# NFC_Card.net
KiCad netlist of a schematic drawn in EasyEDA
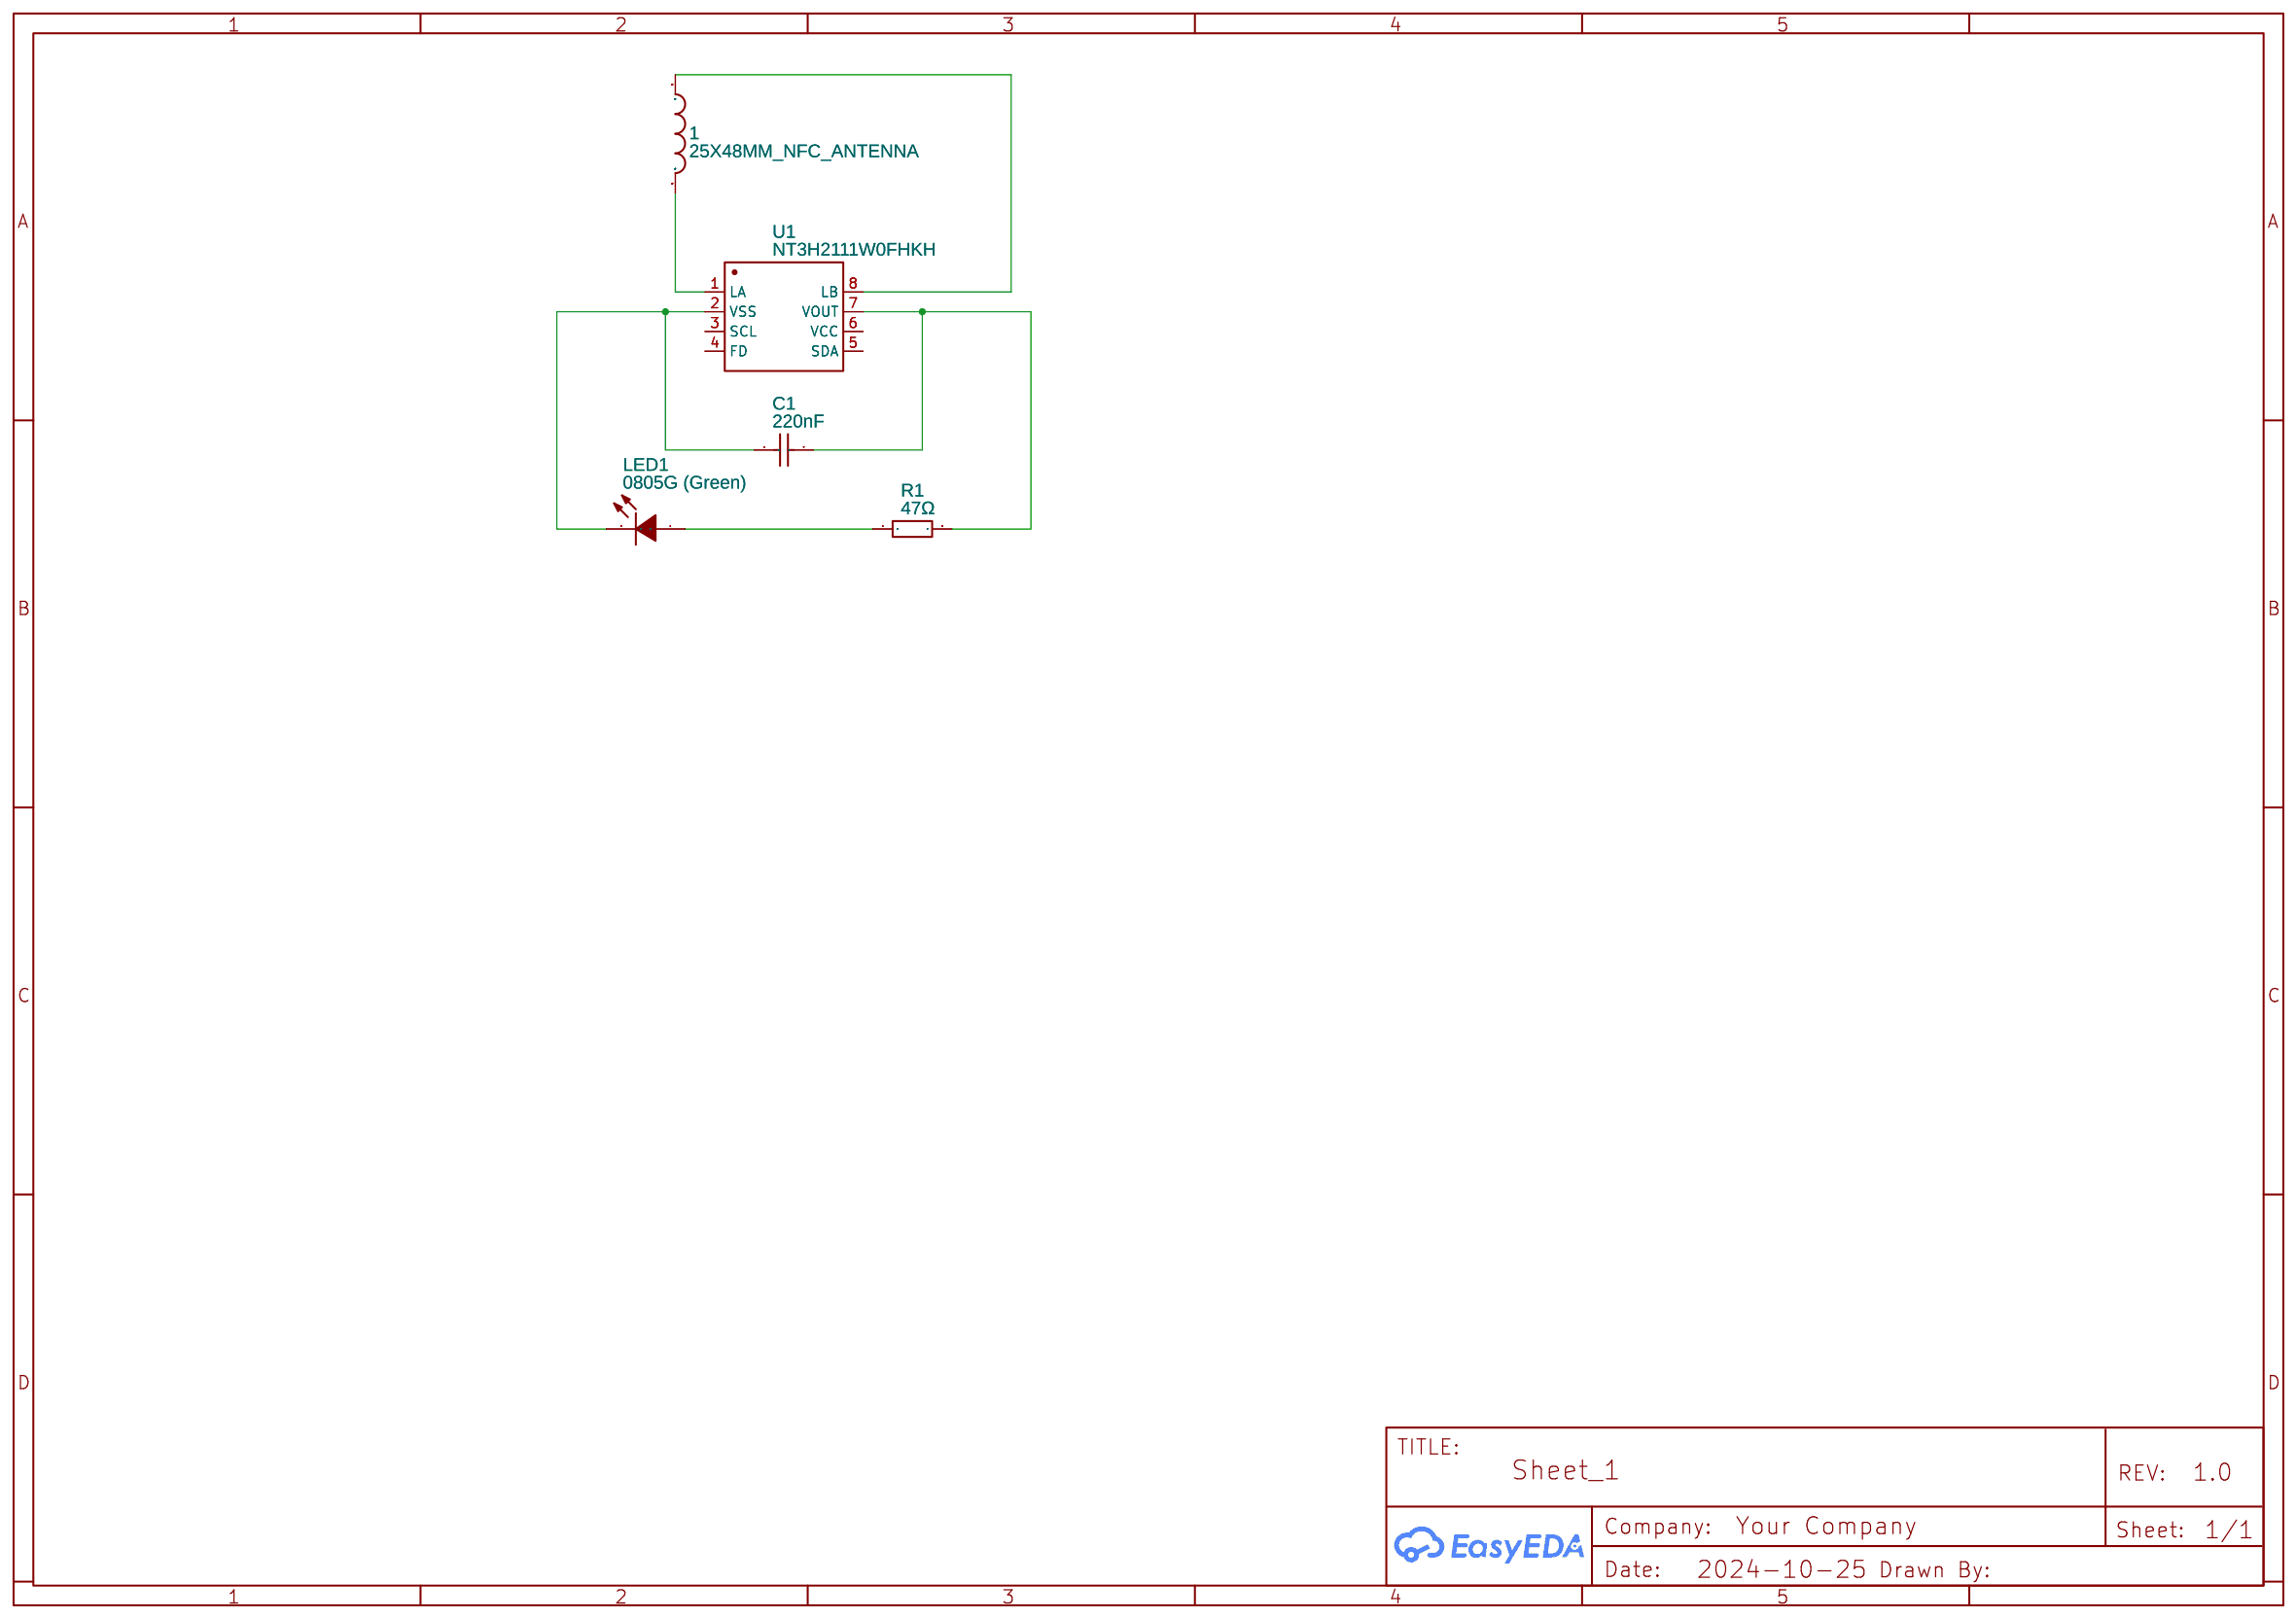
[diagram p0: schematic sheet]

(export (version "E")
  (design (tool "Eeschema 10.0.6"))
  (components
    (comp (ref "1") (value "25X48MM_NFC_ANTENNA") (libsource (lib "") (part "25X48MM_NFC_ANTENNA")))
    (comp (ref "C1")
      (value "220nF")
      (fields
        (field (name "Manufacturer Part") "CL10B224KA8NNNC")
        (field (name "Manufacturer") "SAMSUNG(三星)")
      )
      (libsource (lib "") (part "CL10B224KA8NNNC"))
    )
    (comp (ref "LED1")
      (value "0805G (Green)")
      (fields (field (name "Manufacturer Part") "KT-0805G") (field (name "Manufacturer") "KENTO"))
      (libsource (lib "") (part "0805G (Green)"))
    )
    (comp (ref "R1")
      (value "47Ω")
      (fields
        (field (name "Manufacturer Part") "0603WAF470JT5E")
        (field (name "Manufacturer") "UNI-ROYAL(厚声)")
      )
      (libsource (lib "") (part "0603WAF470JT5E"))
    )
    (comp (ref "U1")
      (value "NT3H2111W0FHKH")
      (fields (field (name "Manufacturer") "NXP(恩智浦)"))
      (libsource (lib "") (part "NT3H2111W0FHKH"))
    )
  )
  (nets
    (net (code "1") (name "Net-(LED1-A)") (class "Default")
      (node (ref "LED1") (pin "1") (pinfunction "A_1") (pintype "unspecified"))
      (node (ref "R1") (pin "1") (pinfunction "1_1") (pintype "input"))
    )
    (net (code "2") (name "Net-(LED1-K)") (class "Default")
      (node (ref "C1") (pin "1") (pinfunction "1_1") (pintype "input"))
      (node (ref "LED1") (pin "2") (pinfunction "K_2") (pintype "unspecified"))
      (node (ref "U1") (pin "2") (pinfunction "VSS_2") (pintype "unspecified"))
    )
    (net (code "3") (name "Net-(U1-LA)") (class "Default")
      (node (ref "1") (pin "P$2") (pinfunction "P$2_P$2") (pintype "bidirectional"))
      (node (ref "U1") (pin "1") (pinfunction "LA_1") (pintype "unspecified"))
    )
    (net (code "4") (name "Net-(U1-LB)") (class "Default")
      (node (ref "1") (pin "P$1") (pinfunction "P$1_P$1") (pintype "bidirectional"))
      (node (ref "U1") (pin "8") (pinfunction "LB_8") (pintype "unspecified"))
    )
    (net (code "5") (name "Net-(U1-VOUT)") (class "Default")
      (node (ref "C1") (pin "2") (pinfunction "2_2") (pintype "input"))
      (node (ref "R1") (pin "2") (pinfunction "2_2") (pintype "input"))
      (node (ref "U1") (pin "7") (pinfunction "VOUT_7") (pintype "unspecified"))
    )
    (net (code "6") (name "unconnected-(U1-FD-Pad4)") (class "Default")
      (node (ref "U1") (pin "4") (pinfunction "FD_4") (pintype "unspecified"))
    )
    (net (code "7") (name "unconnected-(U1-SCL-Pad3)") (class "Default")
      (node (ref "U1") (pin "3") (pinfunction "SCL_3") (pintype "unspecified"))
    )
    (net (code "8") (name "unconnected-(U1-SDA-Pad5)") (class "Default")
      (node (ref "U1") (pin "5") (pinfunction "SDA_5") (pintype "unspecified"))
    )
    (net (code "9") (name "unconnected-(U1-VCC-Pad6)") (class "Default")
      (node (ref "U1") (pin "6") (pinfunction "VCC_6") (pintype "unspecified"))
    )
  )
)
